# Sheet2.net
KiCad netlist of a schematic drawn in Altium Designer
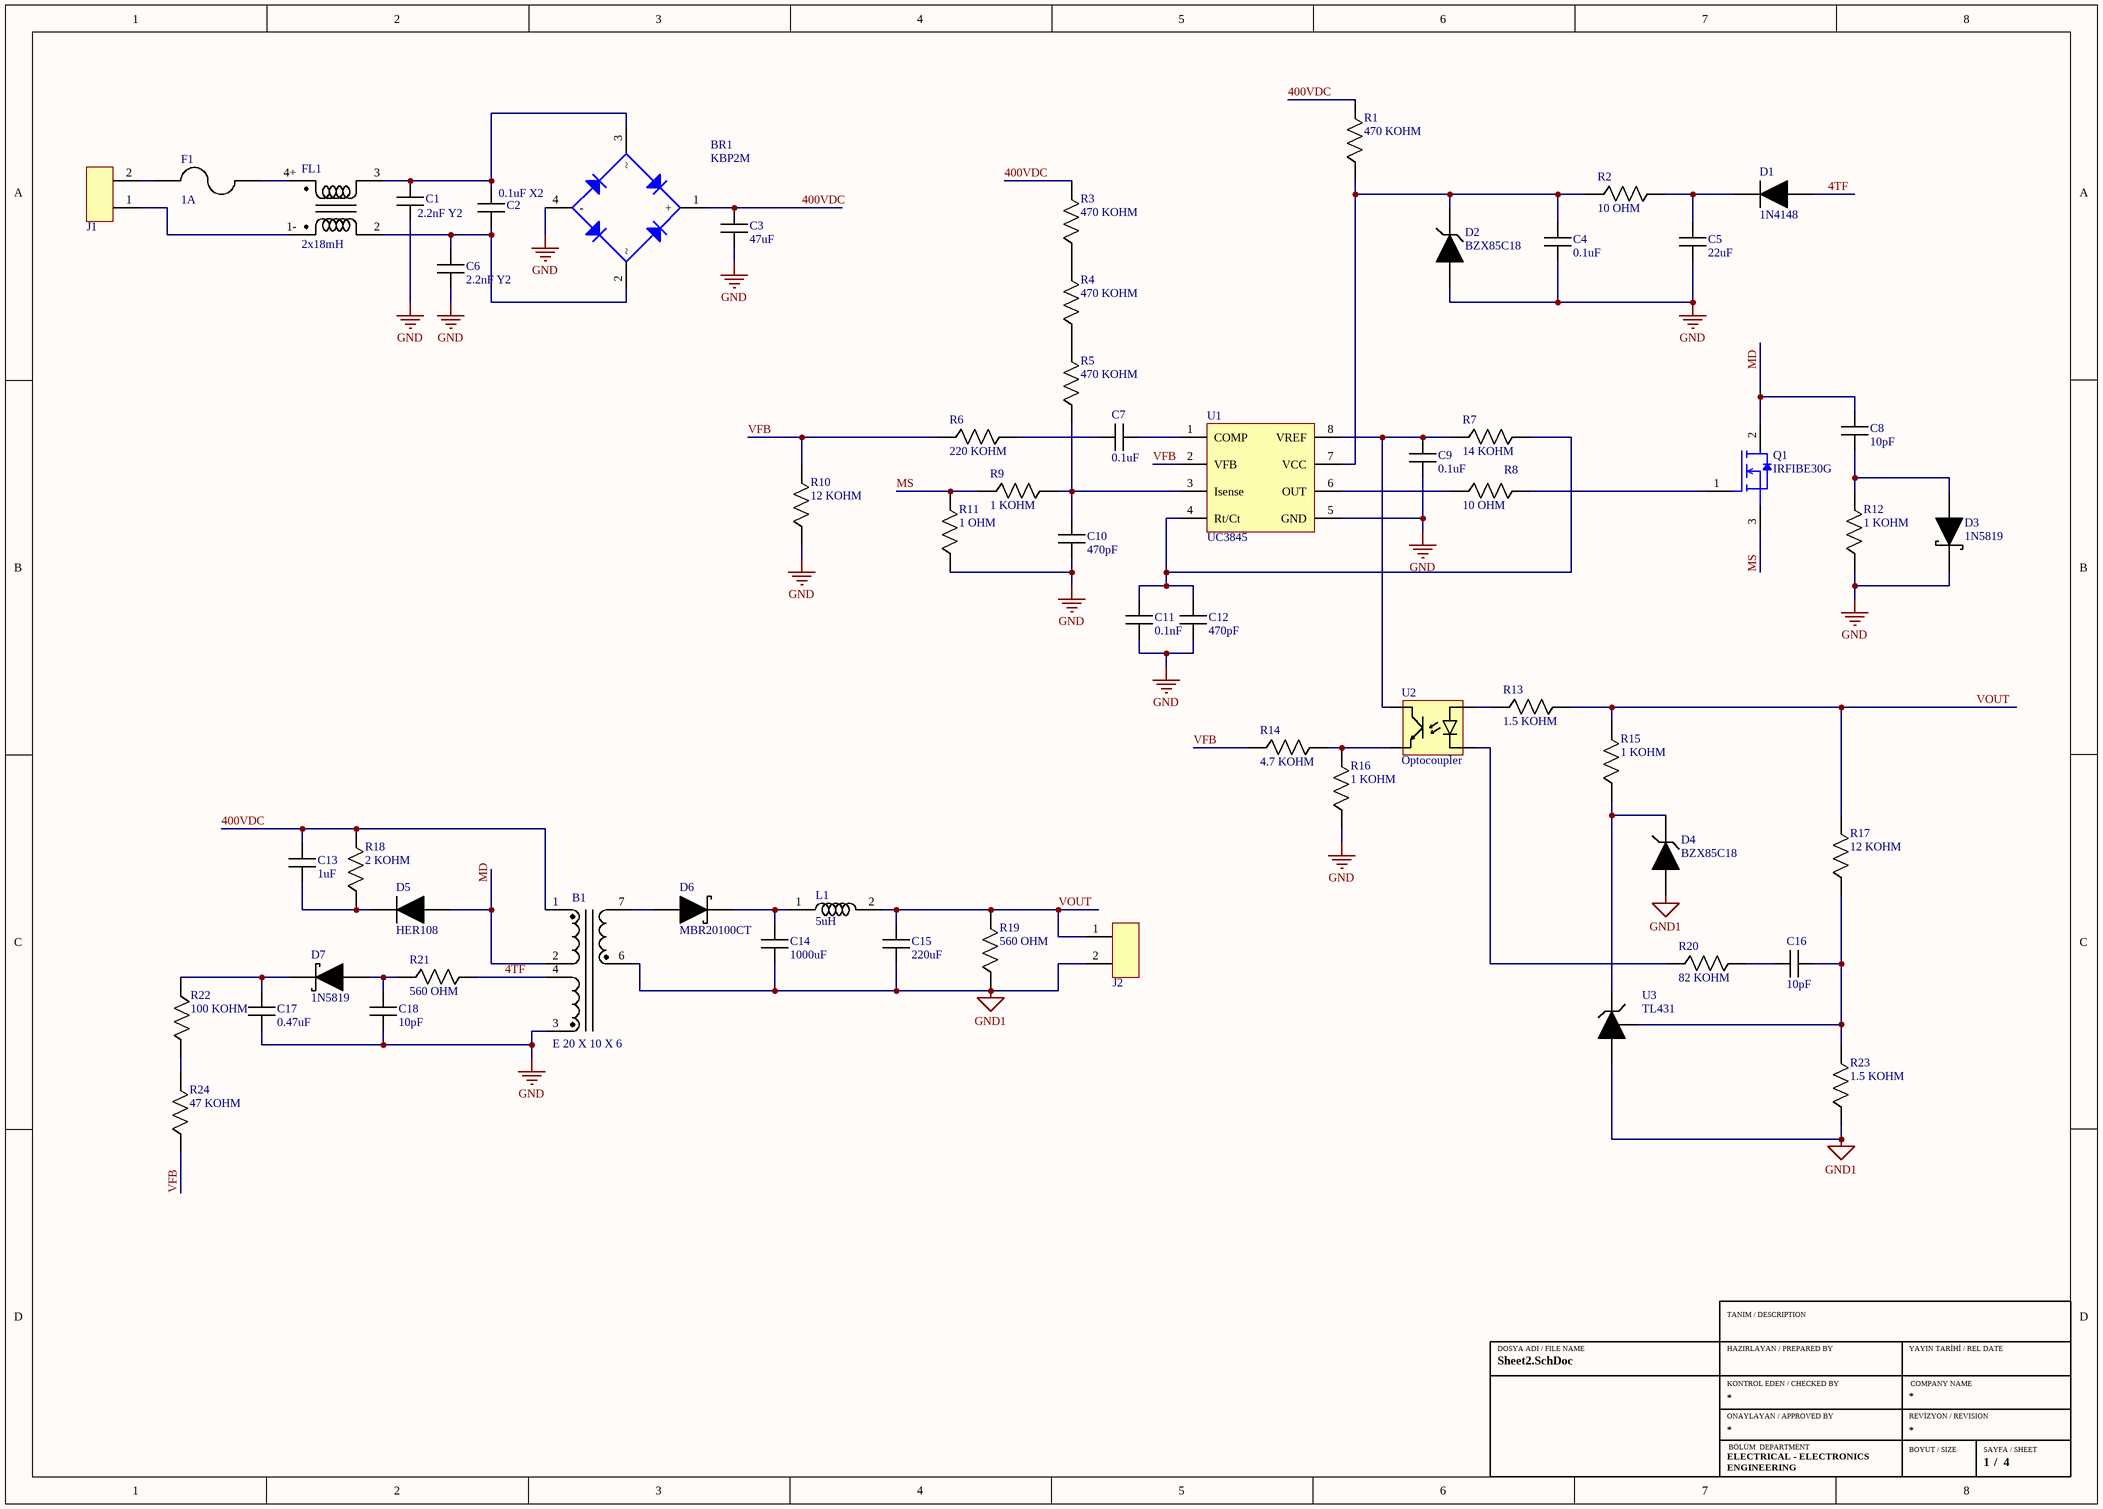
[diagram p0: Sheet2.SchDoc]

(export (version "E")
  (design (tool "Eeschema 10.0.6"))
  (components
    (comp (ref "B1")
      (value "E 20 X 10 X 6")
      (footprint "BOBBIN")
      (description "Ferrite Cores & Accessories E20/10/6 N27LP 0.250 MM\r\nB66311G0000X127")
      (fields
        (field (name "MANUFACTURER") "TDK EPCOS")
        (field (name "MANUFACTURER PART NUMBER") "B66208-B1110-T1")
      )
      (libsource (lib "Integrated_Library2") (part "Transformer"))
    )
    (comp (ref "BR1")
      (value "KBP2M")
      (footprint "KBP2M")
      (description "Bridge Rectifier Single Phase Standard 1 kV Through Hole KBP")
      (fields
        (field (name "MANUFACTURER") "Pan Jit")
        (field (name "MANUFACTURER PART NUMBER") "KBP2MI_T0_00101")
      )
      (libsource (lib "Integrated_Library2") (part "KBP2MI_T0_00101"))
    )
    (comp (ref "C1")
      (value "2.2nF Y2")
      (footprint "Y2-RADIAL")
      (description "CAP FILM 2.2nF 10% 400VAC RADIAL")
      (libsource (lib "Integrated_Library2") (part "CAP FILM Y2 2200pF/400VAC"))
    )
    (comp (ref "C2")
      (value "0.1uF X2")
      (footprint "X2-Radial")
      (description "0.1 µF Film Capacitor 310V Polypropylene (PP), Metallized Radial")
      (libsource (lib "Integrated_Library2") (part "Film Cap X2 0.1uF/310VAC"))
    )
    (comp (ref "C3")
      (value "47uF")
      (footprint "CAP ALU 47UF,400VDC")
      (description "CAP ALU 47uF/400VDC")
      (libsource (lib "Schlib2") (part "CAP ALU 47uF/400VDC"))
    )
    (comp (ref "C4")
      (value "0.1uF")
      (footprint "CAP CER 100nF")
      (description "CAP CER 0.1uF")
      (libsource (lib "Integrated_Library2") (part "CAP CER 0.1uF"))
    )
    (comp (ref "C5")
      (value "22uF")
      (footprint "CAP ALU 22uF")
      (description "CAP ALU 22uF")
      (libsource (lib "Integrated_Library2") (part "CAP ALU 22uF"))
    )
    (comp (ref "C6")
      (value "2.2nF Y2")
      (footprint "Y2-RADIAL")
      (description "CAP FILM 2.2nF 10% 400VAC RADIAL")
      (libsource (lib "Integrated_Library2") (part "CAP FILM Y2 2200pF/400VAC"))
    )
    (comp (ref "C7")
      (value "0.1uF")
      (footprint "CAP CER 100nF")
      (description "Cap Ceramic 0.1uF 50V Z5U 20% Radial 5.08mm 85C T/R")
      (fields
        (field (name "MANUFACTURER") "KEMET")
        (field (name "MANUFACTURER PART NUMBER") "C322C104M5U5TA7301")
      )
      (libsource (lib "Integrated_Library2") (part "CAP CER 100nF"))
    )
    (comp (ref "C8")
      (value "10pF")
      (footprint "CAP ALU 1uF")
      (description "CAP CER 10pF")
      (libsource (lib "Integrated_Library2") (part "CAP CER 10pF"))
    )
    (comp (ref "C9")
      (value "0.1uF")
      (footprint "CAP CER 100nF")
      (description "Cap Ceramic 0.1uF 50V Z5U 20% Radial 5.08mm 85C T/R")
      (fields
        (field (name "MANUFACTURER") "KEMET")
        (field (name "MANUFACTURER PART NUMBER") "C322C104M5U5TA7301")
      )
      (libsource (lib "Integrated_Library2") (part "CAP CER 100nF"))
    )
    (comp (ref "C10")
      (value "470pF")
      (footprint "CAP ALU 1uF")
      (description "CAP CER 470pF")
      (libsource (lib "Integrated_Library2") (part "CAP CER 470pF"))
    )
    (comp (ref "C11")
      (value "0.1nF")
      (footprint "CAP CER 100nF")
      (description "CAP CER 0.1nF")
      (libsource (lib "Integrated_Library2") (part "CAP CER 0.1nF"))
    )
    (comp (ref "C12")
      (value "470pF")
      (footprint "CAP ALU 1uF")
      (description "CAP CER 470pF")
      (libsource (lib "Integrated_Library2") (part "CAP CER 470pF"))
    )
    (comp (ref "C13")
      (value "1uF")
      (footprint "CAP ALU 1uF")
      (description "CAP ALUM 1UF 20% 50V RADIAL WCAP-ATG5 Aluminum Electrolytic Capacitors")
      (fields
        (field (name "MANUFACTURER") "Wurth Electronics")
        (field (name "MANUFACTURER PART NUMBER") "860020672005")
      )
      (libsource (lib "Integrated_Library2") (part "CAP ALU 1uF/50V"))
    )
    (comp (ref "C14")
      (value "1000uF")
      (footprint "CAP ALU 1000uF/16V")
      (description "Cap Aluminum Lytic 1000uF 16V 20% (10 X 16mm) Radial 5mm 1760mA 10000h 105C Bulk")
      (fields
        (field (name "MANUFACTURER") "Rubycon")
        (field (name "MANUFACTURER PART NUMBER") "16ZLH1000MEFC10X16")
      )
      (libsource (lib "Integrated_Library2") (part "CAP ALU 1000uF"))
    )
    (comp (ref "C15")
      (value "220uF")
      (footprint "CAP ALU 220uF/16v")
      (description "Aluminum Electrolytic Capacitor, 220uF 16 V, BT Series 5000h 10 x 12.5mm")
      (fields
        (field (name "MANUFACTURER") "Nichicon")
        (field (name "MANUFACTURER PART NUMBER") "UBT1C221MPD8")
      )
      (libsource (lib "Integrated_Library2") (part "CAP ALU 220uF"))
    )
    (comp (ref "C16")
      (value "10pF")
      (footprint "CAP ALU 1uF")
      (description "CAP CER 10pF")
      (libsource (lib "Integrated_Library2") (part "CAP CER 10pF"))
    )
    (comp (ref "C17")
      (value "0.47uF")
      (footprint "CAP ALU 1uF")
      (description "CAP ALU 0.47uF")
      (libsource (lib "Integrated_Library2") (part "CAP ALU 0.47uF"))
    )
    (comp (ref "C18")
      (value "10pF")
      (footprint "CAP ALU 1uF")
      (description "CAP CER 10pF")
      (libsource (lib "Integrated_Library2") (part "CAP CER 10pF"))
    )
    (comp (ref "D1")
      (value "1N4148")
      (footprint "DO-35")
      (description "1N4148 Series 500 mW 100 V Max Reverse Voltage 200 mA Small Signal Diode -DO-35")
      (fields (field (name "MANUFACTURER") "ON Semiconductor / Fairchild") (field (name "VOLTAGE") "100V"))
      (libsource (lib "Integrated_Library2") (part "DIODE 1N4148"))
    )
    (comp (ref "D2")
      (value "BZX85C18")
      (footprint "Do-41")
      (description "BZX85C Series 1 W 18 V 200 mA Through Hole Zener Diode - DO-41")
      (fields (field (name "MANUFACTURER") "ON Semiconductor / Fairchild"))
      (libsource (lib "Integrated_Library2") (part "BZX85C18"))
    )
    (comp (ref "D3")
      (value "1N5819")
      (footprint "Do-41")
      (description "Rectifier Diode, Schottky, 1 Phase, 1 Element, 1A, 40V V(RRM), Silicon, DO-41")
      (fields (field (name "MANUFACTURER") "STMicroelectronics"))
      (libsource (lib "Integrated_Library2") (part "1N5819"))
    )
    (comp (ref "D4")
      (value "BZX85C18")
      (footprint "Do-41")
      (description "BZX85C Series 1 W 18 V 200 mA Through Hole Zener Diode - DO-41")
      (fields (field (name "MANUFACTURER") "ON Semiconductor / Fairchild"))
      (libsource (lib "Integrated_Library2") (part "BZX85C18"))
    )
    (comp (ref "D5")
      (value "HER108")
      (footprint "Do-41")
      (description "75ns, 1A, 1000V, High Efficient Recovery Rectifier")
      (fields
        (field (name "MANUFACTURER") "Taiwan Semiconductor")
        (field (name "MANUFACTURER PART NUMBER") "HER108G A0G")
      )
      (libsource (lib "Integrated_Library2") (part "Diode 1000V-1A"))
    )
    (comp (ref "D6")
      (value "MBR20100CT")
      (footprint "TO-220")
      (description "Dual Common-Cathode High-Voltage Schottky Rectifier ¦ DIODE ARRAY SCHOTTKY 100V TO220")
      (fields
        (field (name "MANUFACTURER") "Vishay Semiconductors")
        (field (name "MANUFACTURER PART NUMBER") "MBR20100CT-E3/4W")
      )
      (libsource (lib "Integrated_Library2") (part "MBR20100CT"))
    )
    (comp (ref "D7")
      (value "1N5819")
      (footprint "Do-41")
      (description "Rectifier Diode, Schottky, 1 Phase, 1 Element, 1A, 40V V(RRM), Silicon, DO-41")
      (fields (field (name "MANUFACTURER") "STMicroelectronics"))
      (libsource (lib "Integrated_Library2") (part "1N5819"))
    )
    (comp (ref "F1")
      (value "1A")
      (footprint "fUSE")
      (description "1A FUSE")
      (libsource (lib "Integrated_Library2") (part "Fuse"))
    )
    (comp (ref "FL1")
      (value "2x18mH")
      (footprint "2x18mH")
      (description "2x18mH choke")
      (libsource (lib "Schlib2") (part "EMI Filter"))
    )
    (comp (ref "J1") (value "HEADER x2") (footprint "HEADER X2") (libsource (lib "") (part "HEADER x2_1")))
    (comp (ref "J2")
      (value "HEADER x2")
      (footprint "HEADER X2")
      (libsource (lib "Integrated_Library2") (part "HEADER x2"))
    )
    (comp (ref "L1")
      (value "5uH")
      (footprint "IND-RADIAL")
      (description "Fixed Ind 5UH 20A 5 Mohm Th")
      (fields
        (field (name "MANUFACTURER") "Hammond Manufacturing")
        (field (name "MANUFACTURER PART NUMBER") "1539M10")
      )
      (libsource (lib "Integrated_Library2") (part "IND RADIAL 5uH"))
    )
    (comp (ref "Q1")
      (value "IRFIBE30G")
      (footprint "TO-220")
      (description "Single N-Channel 800 V 3 Ohms Flange Mount Power Mosfet - TO-220FP")
      (fields (field (name "MANUFACTURER") "Vishay") (field (name "MANUFACTURER PART NUMBER") "IRFIBE30GPBF"))
      (libsource (lib "Integrated_Library2") (part "IRFIBE30G"))
    )
    (comp (ref "R1")
      (value "470 KOHM")
      (footprint "RES")
      (description "RES 470 KOHM")
      (libsource (lib "Integrated_Library2") (part "RES 470 KOHM"))
    )
    (comp (ref "R2")
      (value "10 OHM")
      (footprint "RES")
      (description "RES 10 OHM")
      (libsource (lib "Integrated_Library2") (part "RES 10 OHM"))
    )
    (comp (ref "R3")
      (value "470 KOHM")
      (footprint "RES")
      (description "RES 470 KOHM")
      (libsource (lib "Integrated_Library2") (part "RES 470 KOHM"))
    )
    (comp (ref "R4")
      (value "470 KOHM")
      (footprint "RES")
      (description "RES 470 KOHM")
      (libsource (lib "Integrated_Library2") (part "RES 470 KOHM"))
    )
    (comp (ref "R5")
      (value "470 KOHM")
      (footprint "RES")
      (description "RES 470 KOHM")
      (libsource (lib "Integrated_Library2") (part "RES 470 KOHM"))
    )
    (comp (ref "R6")
      (value "220 KOHM")
      (footprint "RES")
      (description "RES 220 KOHM")
      (libsource (lib "Integrated_Library2") (part "RES 220 KOHM"))
    )
    (comp (ref "R7")
      (value "14 KOHM")
      (footprint "RES")
      (description "RES 14 KOHM")
      (libsource (lib "Integrated_Library2") (part "RES 14 KOHM"))
    )
    (comp (ref "R8")
      (value "10 OHM")
      (footprint "RES")
      (description "RES 10 OHM")
      (libsource (lib "Integrated_Library2") (part "RES 10 OHM"))
    )
    (comp (ref "R9")
      (value "1 KOHM")
      (footprint "RES")
      (description "RES 1 KOHM")
      (libsource (lib "Integrated_Library2") (part "RES 1 KOHM"))
    )
    (comp (ref "R10")
      (value "12 KOHM")
      (footprint "RES")
      (description "RES 12 KOHM")
      (libsource (lib "Integrated_Library2") (part "RES 12 KOHM"))
    )
    (comp (ref "R11")
      (value "1 OHM")
      (footprint "RES")
      (description "RES 1 OHM")
      (libsource (lib "Integrated_Library2") (part "RES 1 OHM"))
    )
    (comp (ref "R12")
      (value "1 KOHM")
      (footprint "RES")
      (description "RES 1 KOHM")
      (libsource (lib "Integrated_Library2") (part "RES 1 KOHM"))
    )
    (comp (ref "R13")
      (value "1.5 KOHM")
      (footprint "RES")
      (description "RES 1.5 KOHM")
      (libsource (lib "Integrated_Library2") (part "RES 1.5 KOHM"))
    )
    (comp (ref "R14")
      (value "4.7 KOHM")
      (footprint "RES")
      (description "RES 4.7 KOHM")
      (libsource (lib "Integrated_Library2") (part "RES 4.7 KOHM"))
    )
    (comp (ref "R15")
      (value "1 KOHM")
      (footprint "RES")
      (description "RES 1 KOHM")
      (libsource (lib "Integrated_Library2") (part "RES 1 KOHM"))
    )
    (comp (ref "R16")
      (value "1 KOHM")
      (footprint "RES")
      (description "RES 1 KOHM")
      (libsource (lib "Integrated_Library2") (part "RES 1 KOHM"))
    )
    (comp (ref "R17")
      (value "12 KOHM")
      (footprint "RES")
      (description "RES 12 KOHM")
      (libsource (lib "Integrated_Library2") (part "RES 12 KOHM"))
    )
    (comp (ref "R18")
      (value "2 KOHM")
      (footprint "RES")
      (description "RES 2 KOHM")
      (libsource (lib "Integrated_Library2") (part "RES 2 KOHM"))
    )
    (comp (ref "R19")
      (value "560 OHM")
      (footprint "RES")
      (description "RES 560 OHM")
      (libsource (lib "Integrated_Library2") (part "RES 560 OHM"))
    )
    (comp (ref "R20")
      (value "82 KOHM")
      (footprint "RES")
      (description "RES 82 KOHM")
      (libsource (lib "Integrated_Library2") (part "RES 82 KOHM"))
    )
    (comp (ref "R21")
      (value "560 OHM")
      (footprint "RES")
      (description "RES 560 OHM")
      (libsource (lib "Integrated_Library2") (part "RES 560 OHM"))
    )
    (comp (ref "R22")
      (value "100 KOHM")
      (footprint "RES")
      (description "RES 100 KOHM")
      (libsource (lib "Integrated_Library2") (part "RES 100 KOHM"))
    )
    (comp (ref "R23")
      (value "1.5 KOHM")
      (footprint "RES")
      (description "RES 1.5 KOHM")
      (libsource (lib "Integrated_Library2") (part "RES 1.5 KOHM"))
    )
    (comp (ref "R24")
      (value "47 KOHM")
      (footprint "RES")
      (description "RES 47 KOHM")
      (libsource (lib "Integrated_Library2") (part "RES 47 KOHM"))
    )
    (comp (ref "U1")
      (value "UC3845")
      (footprint "8-DIP")
      (fields
        (field (name "MANUFACTURER") "STMicroelectronics")
        (field (name "MANUFACTURER PART NUMBER") "UC3845BN")
      )
      (libsource (lib "Integrated_Library2") (part "UC3845"))
    )
    (comp (ref "U2")
      (value "Optocoupler")
      (footprint "4-DIP")
      (description "Optocoupler DC-IN 1-CH Darlington DC-OUT 4-Pin PDIP Magazine")
      (fields (field (name "MANUFACTURER") "Renesas") (field (name "MANUFACTURER PART NUMBER") "PS2502-1-A"))
      (libsource (lib "Integrated_Library2") (part "Optocoupler"))
    )
    (comp (ref "U3")
      (value "TL431")
      (footprint "TL431 - th - TO92-3")
      (description "Shunt Voltage Reference IC Adjustable 2.495V 36 VV ±1% 100 mA TO-92-3")
      (fields
        (field (name "MANUFACTURER") "Texas Instruments")
        (field (name "MANUFACTURER PART NUMBER") "TL431ACLPR")
      )
      (libsource (lib "Integrated_Library2") (part "TL431 - th"))
    )
  )
  (nets
    (net (code "1") (name "/4TF") (class "Default")
      (node (ref "B1") (pin "4") (pinfunction "4_4") (pintype "passive"))
      (node (ref "D1") (pin "A") (pinfunction "A_A") (pintype "passive"))
      (node (ref "R21") (pin "2") (pinfunction "2_2") (pintype "passive"))
    )
    (net (code "2") (name "/400VDC") (class "Default")
      (node (ref "B1") (pin "1") (pinfunction "1_1") (pintype "passive"))
      (node (ref "BR1") (pin "1") (pinfunction "+_1") (pintype "passive"))
      (node (ref "C13") (pin "2") (pinfunction "-_2") (pintype "passive"))
      (node (ref "C3") (pin "2") (pinfunction "+_2") (pintype "passive"))
      (node (ref "R1") (pin "2") (pinfunction "2_2") (pintype "passive"))
      (node (ref "R18") (pin "2") (pinfunction "2_2") (pintype "passive"))
      (node (ref "R3") (pin "2") (pinfunction "2_2") (pintype "passive"))
    )
    (net (code "3") (name "/MD") (class "Default")
      (node (ref "B1") (pin "2") (pinfunction "2_2") (pintype "passive"))
      (node (ref "C8") (pin "2") (pinfunction "-_2") (pintype "passive"))
      (node (ref "D5") (pin "A") (pinfunction "A_A") (pintype "passive"))
      (node (ref "Q1") (pin "2") (pinfunction "D_2") (pintype "passive"))
    )
    (net (code "4") (name "/MS") (class "Default")
      (node (ref "Q1") (pin "3") (pinfunction "S_3") (pintype "passive"))
      (node (ref "R11") (pin "2") (pinfunction "2_2") (pintype "passive"))
      (node (ref "R9") (pin "1") (pinfunction "1_1") (pintype "passive"))
    )
    (net (code "5") (name "/VFB") (class "Default")
      (node (ref "R10") (pin "2") (pinfunction "2_2") (pintype "passive"))
      (node (ref "R14") (pin "1") (pinfunction "1_1") (pintype "passive"))
      (node (ref "R24") (pin "1") (pinfunction "1_1") (pintype "passive"))
      (node (ref "R6") (pin "1") (pinfunction "1_1") (pintype "passive"))
      (node (ref "U1") (pin "2") (pinfunction "VFB_2") (pintype "passive"))
    )
    (net (code "6") (name "/VOUT") (class "Default")
      (node (ref "C15") (pin "2") (pinfunction "-_2") (pintype "passive"))
      (node (ref "J2") (pin "1") (pinfunction "1_1") (pintype "passive"))
      (node (ref "L1") (pin "2") (pinfunction "2_2") (pintype "passive"))
      (node (ref "R13") (pin "2") (pinfunction "2_2") (pintype "passive"))
      (node (ref "R15") (pin "2") (pinfunction "2_2") (pintype "passive"))
      (node (ref "R17") (pin "2") (pinfunction "2_2") (pintype "passive"))
      (node (ref "R19") (pin "2") (pinfunction "2_2") (pintype "passive"))
    )
    (net (code "7") (name "GND") (class "Default")
      (node (ref "B1") (pin "3") (pinfunction "3_3") (pintype "passive"))
      (node (ref "BR1") (pin "4") (pinfunction "-_4") (pintype "passive"))
      (node (ref "C1") (pin "1") (pinfunction "1_1") (pintype "passive"))
      (node (ref "C10") (pin "1") (pinfunction "+_1") (pintype "passive"))
      (node (ref "C11") (pin "2") (pinfunction "-_2") (pintype "passive"))
      (node (ref "C12") (pin "2") (pinfunction "-_2") (pintype "passive"))
      (node (ref "C17") (pin "1") (pinfunction "+_1") (pintype "passive"))
      (node (ref "C18") (pin "1") (pinfunction "+_1") (pintype "passive"))
      (node (ref "C3") (pin "1") (pinfunction "-_1") (pintype "passive"))
      (node (ref "C4") (pin "1") (pinfunction "+_1") (pintype "passive"))
      (node (ref "C5") (pin "1") (pinfunction "+_1") (pintype "passive"))
      (node (ref "C6") (pin "1") (pinfunction "1_1") (pintype "passive"))
      (node (ref "C9") (pin "1") (pinfunction "+_1") (pintype "passive"))
      (node (ref "D2") (pin "A") (pinfunction "A_A") (pintype "passive"))
      (node (ref "D3") (pin "C") (pinfunction "C_C") (pintype "passive"))
      (node (ref "R10") (pin "1") (pinfunction "1_1") (pintype "passive"))
      (node (ref "R11") (pin "1") (pinfunction "1_1") (pintype "passive"))
      (node (ref "R12") (pin "1") (pinfunction "1_1") (pintype "passive"))
      (node (ref "R16") (pin "1") (pinfunction "1_1") (pintype "passive"))
      (node (ref "U1") (pin "5") (pinfunction "GND_5") (pintype "passive"))
    )
    (net (code "8") (name "GND1") (class "Default")
      (node (ref "B1") (pin "6") (pinfunction "6_6") (pintype "passive"))
      (node (ref "C14") (pin "1") (pinfunction "+_1") (pintype "passive"))
      (node (ref "C15") (pin "1") (pinfunction "+_1") (pintype "passive"))
      (node (ref "D4") (pin "A") (pinfunction "A_A") (pintype "passive"))
      (node (ref "J2") (pin "2") (pinfunction "2_2") (pintype "passive"))
      (node (ref "R19") (pin "1") (pinfunction "1_1") (pintype "passive"))
      (node (ref "R23") (pin "1") (pinfunction "1_1") (pintype "passive"))
      (node (ref "U3") (pin "A") (pinfunction "A_A") (pintype "passive"))
    )
    (net (code "9") (name "Net-(B1-Pad7)") (class "Default")
      (node (ref "B1") (pin "7") (pinfunction "7_7") (pintype "passive"))
      (node (ref "D6") (pin "1") (pinfunction "1_1") (pintype "passive"))
    )
    (net (code "10") (name "Net-(BR1-~-Pad2)") (class "Default")
      (node (ref "BR1") (pin "2") (pinfunction "~_2") (pintype "passive"))
      (node (ref "C2") (pin "1") (pinfunction "1_1") (pintype "passive"))
      (node (ref "C6") (pin "2") (pinfunction "2_2") (pintype "passive"))
      (node (ref "FL1") (pin "2") (pinfunction "2_2") (pintype "passive"))
    )
    (net (code "11") (name "Net-(BR1-~-Pad3)") (class "Default")
      (node (ref "BR1") (pin "3") (pinfunction "~_3") (pintype "passive"))
      (node (ref "C1") (pin "2") (pinfunction "2_2") (pintype "passive"))
      (node (ref "C2") (pin "2") (pinfunction "2_2") (pintype "passive"))
      (node (ref "FL1") (pin "3") (pinfunction "2_3") (pintype "passive"))
    )
    (net (code "12") (name "Net-(C4--)") (class "Default")
      (node (ref "C4") (pin "2") (pinfunction "-_2") (pintype "passive"))
      (node (ref "D2") (pin "C") (pinfunction "C_C") (pintype "passive"))
      (node (ref "R1") (pin "1") (pinfunction "1_1") (pintype "passive"))
      (node (ref "R2") (pin "1") (pinfunction "1_1") (pintype "passive"))
      (node (ref "U1") (pin "7") (pinfunction "VCC_7") (pintype "passive"))
    )
    (net (code "13") (name "Net-(C5--)") (class "Default")
      (node (ref "C5") (pin "2") (pinfunction "-_2") (pintype "passive"))
      (node (ref "D1") (pin "C") (pinfunction "C_C") (pintype "passive"))
      (node (ref "R2") (pin "2") (pinfunction "2_2") (pintype "passive"))
    )
    (net (code "14") (name "Net-(C7-+)") (class "Default")
      (node (ref "C7") (pin "1") (pinfunction "+_1") (pintype "passive"))
      (node (ref "R6") (pin "2") (pinfunction "2_2") (pintype "passive"))
    )
    (net (code "15") (name "Net-(C7--)") (class "Default")
      (node (ref "C7") (pin "2") (pinfunction "-_2") (pintype "passive"))
      (node (ref "U1") (pin "1") (pinfunction "COMP_1") (pintype "passive"))
    )
    (net (code "16") (name "Net-(C8-+)") (class "Default")
      (node (ref "C8") (pin "1") (pinfunction "+_1") (pintype "passive"))
      (node (ref "D3") (pin "A") (pinfunction "A_A") (pintype "passive"))
      (node (ref "R12") (pin "2") (pinfunction "2_2") (pintype "passive"))
    )
    (net (code "17") (name "Net-(C9--)") (class "Default")
      (node (ref "C9") (pin "2") (pinfunction "-_2") (pintype "passive"))
      (node (ref "R7") (pin "1") (pinfunction "1_1") (pintype "passive"))
      (node (ref "U1") (pin "8") (pinfunction "VREF_8") (pintype "passive"))
      (node (ref "U2") (pin "4") (pinfunction "4_4") (pintype "passive"))
    )
    (net (code "18") (name "Net-(C10--)") (class "Default")
      (node (ref "C10") (pin "2") (pinfunction "-_2") (pintype "passive"))
      (node (ref "R5") (pin "1") (pinfunction "1_1") (pintype "passive"))
      (node (ref "R9") (pin "2") (pinfunction "2_2") (pintype "passive"))
      (node (ref "U1") (pin "3") (pinfunction "Isense_3") (pintype "passive"))
    )
    (net (code "19") (name "Net-(C11-+)") (class "Default")
      (node (ref "C11") (pin "1") (pinfunction "+_1") (pintype "passive"))
      (node (ref "C12") (pin "1") (pinfunction "+_1") (pintype "passive"))
      (node (ref "R7") (pin "2") (pinfunction "2_2") (pintype "passive"))
      (node (ref "U1") (pin "4") (pinfunction "Rt/Ct_4") (pintype "passive"))
    )
    (net (code "20") (name "Net-(C13-+)") (class "Default")
      (node (ref "C13") (pin "1") (pinfunction "+_1") (pintype "passive"))
      (node (ref "D5") (pin "C") (pinfunction "C_C") (pintype "passive"))
      (node (ref "R18") (pin "1") (pinfunction "1_1") (pintype "passive"))
    )
    (net (code "21") (name "Net-(C14--)") (class "Default")
      (node (ref "C14") (pin "2") (pinfunction "-_2") (pintype "passive"))
      (node (ref "D6") (pin "2") (pinfunction "2_2") (pintype "passive"))
      (node (ref "L1") (pin "1") (pinfunction "1_1") (pintype "passive"))
    )
    (net (code "22") (name "Net-(C16-+)") (class "Default")
      (node (ref "C16") (pin "1") (pinfunction "+_1") (pintype "passive"))
      (node (ref "R20") (pin "2") (pinfunction "2_2") (pintype "passive"))
    )
    (net (code "23") (name "Net-(C16--)") (class "Default")
      (node (ref "C16") (pin "2") (pinfunction "-_2") (pintype "passive"))
      (node (ref "R17") (pin "1") (pinfunction "1_1") (pintype "passive"))
      (node (ref "R23") (pin "2") (pinfunction "2_2") (pintype "passive"))
      (node (ref "U3") (pin "R") (pinfunction "R_R") (pintype "passive"))
    )
    (net (code "24") (name "Net-(C17--)") (class "Default")
      (node (ref "C17") (pin "2") (pinfunction "-_2") (pintype "passive"))
      (node (ref "D7") (pin "C") (pinfunction "C_C") (pintype "passive"))
      (node (ref "R22") (pin "1") (pinfunction "1_1") (pintype "passive"))
    )
    (net (code "25") (name "Net-(C18--)") (class "Default")
      (node (ref "C18") (pin "2") (pinfunction "-_2") (pintype "passive"))
      (node (ref "D7") (pin "A") (pinfunction "A_A") (pintype "passive"))
      (node (ref "R21") (pin "1") (pinfunction "1_1") (pintype "passive"))
    )
    (net (code "26") (name "Net-(D4-PadC)") (class "Default")
      (node (ref "D4") (pin "C") (pinfunction "C_C") (pintype "passive"))
      (node (ref "R15") (pin "1") (pinfunction "1_1") (pintype "passive"))
      (node (ref "U3") (pin "C") (pinfunction "C_C") (pintype "passive"))
    )
    (net (code "27") (name "Net-(F1-Pad1)") (class "Default")
      (node (ref "F1") (pin "1") (pinfunction "1_1") (pintype "passive"))
      (node (ref "J1") (pin "2") (pinfunction "2_2") (pintype "passive"))
    )
    (net (code "28") (name "Net-(F1-Pad2)") (class "Default")
      (node (ref "F1") (pin "2") (pinfunction "2_2") (pintype "passive"))
      (node (ref "FL1") (pin "4+") (pinfunction "4+_4+") (pintype "passive"))
    )
    (net (code "29") (name "Net-(FL1-1)") (class "Default")
      (node (ref "FL1") (pin "1-") (pinfunction "1_1-") (pintype "passive"))
      (node (ref "J1") (pin "1") (pinfunction "1_1") (pintype "passive"))
    )
    (net (code "30") (name "Net-(Q1-G)") (class "Default")
      (node (ref "Q1") (pin "1") (pinfunction "G_1") (pintype "passive"))
      (node (ref "R8") (pin "2") (pinfunction "2_2") (pintype "passive"))
    )
    (net (code "31") (name "Net-(R3-Pad1)") (class "Default")
      (node (ref "R3") (pin "1") (pinfunction "1_1") (pintype "passive"))
      (node (ref "R4") (pin "2") (pinfunction "2_2") (pintype "passive"))
    )
    (net (code "32") (name "Net-(R4-Pad1)") (class "Default")
      (node (ref "R4") (pin "1") (pinfunction "1_1") (pintype "passive"))
      (node (ref "R5") (pin "2") (pinfunction "2_2") (pintype "passive"))
    )
    (net (code "33") (name "Net-(R13-Pad1)") (class "Default")
      (node (ref "R13") (pin "1") (pinfunction "1_1") (pintype "passive"))
      (node (ref "U2") (pin "1") (pinfunction "1_1") (pintype "passive"))
    )
    (net (code "34") (name "Net-(R14-Pad2)") (class "Default")
      (node (ref "R14") (pin "2") (pinfunction "2_2") (pintype "passive"))
      (node (ref "R16") (pin "2") (pinfunction "2_2") (pintype "passive"))
      (node (ref "U2") (pin "3") (pinfunction "3_3") (pintype "passive"))
    )
    (net (code "35") (name "Net-(R20-Pad1)") (class "Default")
      (node (ref "R20") (pin "1") (pinfunction "1_1") (pintype "passive"))
      (node (ref "U2") (pin "2") (pinfunction "2_2") (pintype "passive"))
    )
    (net (code "36") (name "Net-(R22-Pad2)") (class "Default")
      (node (ref "R22") (pin "2") (pinfunction "2_2") (pintype "passive"))
      (node (ref "R24") (pin "2") (pinfunction "2_2") (pintype "passive"))
    )
    (net (code "37") (name "Net-(U1-OUT)") (class "Default")
      (node (ref "R8") (pin "1") (pinfunction "1_1") (pintype "passive"))
      (node (ref "U1") (pin "6") (pinfunction "OUT_6") (pintype "passive"))
    )
  )
)
